# SilentStepStick-TMC2100_v13.net
KiCad netlist of a schematic drawn in EAGLE
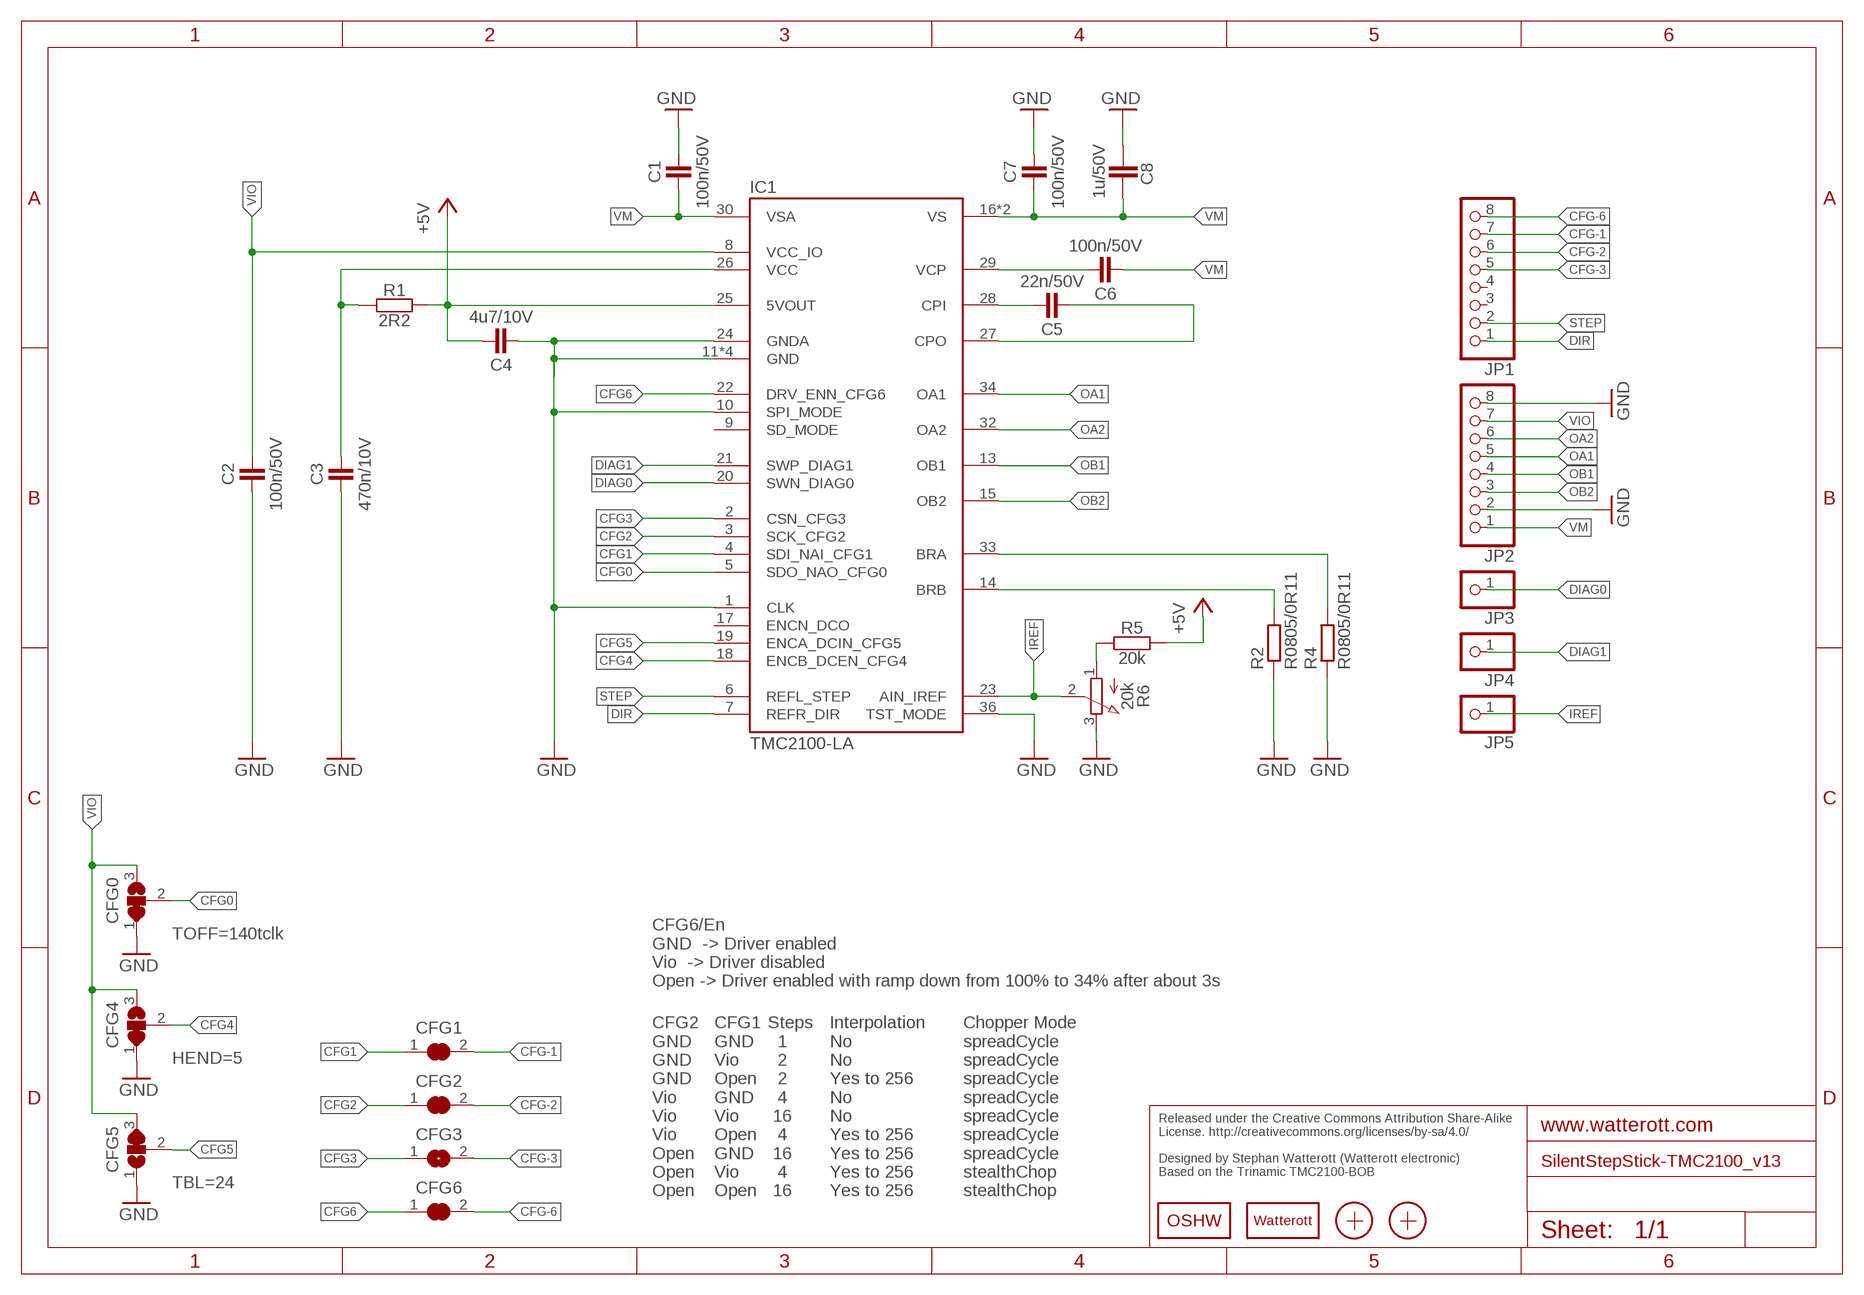
[diagram p0: schematic, sheet 1]

(export (version "E")
  (design (tool "Eeschema 10.0.6"))
  (components
    (comp (ref "C1")
      (value "100n/50V")
      (footprint "eagle-import:C0402")
      (libsource (lib "eagle-import") (part "CAPACITOR-0402"))
    )
    (comp (ref "C2")
      (value "100n/50V")
      (footprint "eagle-import:C0402")
      (libsource (lib "eagle-import") (part "CAPACITOR-0402"))
    )
    (comp (ref "C3")
      (value "470n/10V")
      (footprint "eagle-import:C0402")
      (libsource (lib "eagle-import") (part "CAPACITOR-0402"))
    )
    (comp (ref "C4")
      (value "4u7/10V")
      (footprint "eagle-import:C0402")
      (libsource (lib "eagle-import") (part "CAPACITOR-0402"))
    )
    (comp (ref "C5")
      (value "22n/50V")
      (footprint "eagle-import:C0402")
      (libsource (lib "eagle-import") (part "CAPACITOR-0402"))
    )
    (comp (ref "C6")
      (value "100n/50V")
      (footprint "eagle-import:C0402")
      (libsource (lib "eagle-import") (part "CAPACITOR-0402"))
    )
    (comp (ref "C7")
      (value "100n/50V")
      (footprint "eagle-import:C0402")
      (libsource (lib "eagle-import") (part "CAPACITOR-0402"))
    )
    (comp (ref "C8")
      (value "1u/50V")
      (footprint "eagle-import:C0603")
      (libsource (lib "eagle-import") (part "C-EUC0603"))
    )
    (comp (ref "CFG0")
      (value "JUMPER3-0201")
      (footprint "eagle-import:JUMPER3-0201")
      (libsource (lib "eagle-import") (part "JUMPER3-0201"))
    )
    (comp (ref "CFG1")
      (value "JUMPER2-0201")
      (footprint "eagle-import:JUMPER2-0201")
      (libsource (lib "eagle-import") (part "JUMPER2-0201"))
    )
    (comp (ref "CFG2")
      (value "JUMPER2-0201")
      (footprint "eagle-import:JUMPER2-0201")
      (libsource (lib "eagle-import") (part "JUMPER2-0201"))
    )
    (comp (ref "CFG3")
      (value "JUMPER2-0201")
      (footprint "eagle-import:JUMPER2-0201")
      (libsource (lib "eagle-import") (part "JUMPER2-0201"))
    )
    (comp (ref "CFG4")
      (value "JUMPER3-0201")
      (footprint "eagle-import:JUMPER3-0201")
      (libsource (lib "eagle-import") (part "JUMPER3-0201"))
    )
    (comp (ref "CFG5")
      (value "JUMPER3-0201")
      (footprint "eagle-import:JUMPER3-0201")
      (libsource (lib "eagle-import") (part "JUMPER3-0201"))
    )
    (comp (ref "CFG6")
      (value "JUMPER2-0201")
      (footprint "eagle-import:JUMPER2-0201")
      (libsource (lib "eagle-import") (part "JUMPER2-0201"))
    )
    (comp (ref "IC1")
      (value "TMC2100-LA")
      (footprint "eagle-import:QFN36-PAD")
      (libsource (lib "eagle-import") (part "TMC21X0-LA"))
    )
    (comp (ref "JP1")
      (value "PINHD-1X08_2.54-S")
      (footprint "eagle-import:1X08-S")
      (libsource (lib "eagle-import") (part "PINHD-1X08_2.54-S"))
    )
    (comp (ref "JP2")
      (value "PINHD-1X08_2.54-S")
      (footprint "eagle-import:1X08-S")
      (libsource (lib "eagle-import") (part "PINHD-1X08_2.54-S"))
    )
    (comp (ref "JP3")
      (value "PINHD-1X1")
      (footprint "eagle-import:1X01")
      (libsource (lib "eagle-import") (part "PINHD-1X1"))
    )
    (comp (ref "JP4")
      (value "PINHD-1X1")
      (footprint "eagle-import:1X01")
      (libsource (lib "eagle-import") (part "PINHD-1X1"))
    )
    (comp (ref "JP5")
      (value "PINHD-1X1")
      (footprint "eagle-import:1X01")
      (libsource (lib "eagle-import") (part "PINHD-1X1"))
    )
    (comp (ref "LOGO1")
      (value "OSHW_LOGOX0070")
      (footprint "eagle-import:OSHW_6X70")
      (libsource (lib "eagle-import") (part "OSHW_LOGOX0070"))
    )
    (comp (ref "LOGO2")
      (value "LOGO-S_PLACE_M")
      (footprint "eagle-import:SPARK_TPLACE_M")
      (libsource (lib "eagle-import") (part "LOGO-S_PLACE_M"))
    )
    (comp (ref "R1")
      (value "2R2")
      (footprint "eagle-import:C0402")
      (libsource (lib "eagle-import") (part "RESISTOR-0402"))
    )
    (comp (ref "R2")
      (value "R0805/0R11")
      (footprint "eagle-import:M0805")
      (libsource (lib "eagle-import") (part "R-EU_M0805"))
    )
    (comp (ref "R4")
      (value "R0805/0R11")
      (footprint "eagle-import:M0805")
      (libsource (lib "eagle-import") (part "R-EU_M0805"))
    )
    (comp (ref "R5")
      (value "20k")
      (footprint "eagle-import:C0402")
      (libsource (lib "eagle-import") (part "RESISTOR-0402"))
    )
    (comp (ref "R6")
      (value "20k")
      (footprint "eagle-import:POT_EVM3R")
      (libsource (lib "eagle-import") (part "POT-EVM3R"))
    )
    (comp (ref "X1")
      (value "PASSER-07")
      (footprint "eagle-import:PASSER_07MM")
      (libsource (lib "eagle-import") (part "PASSER-07"))
    )
    (comp (ref "X2")
      (value "PASSER-07")
      (footprint "eagle-import:PASSER_07MM")
      (libsource (lib "eagle-import") (part "PASSER-07"))
    )
  )
  (nets
    (net (code "1") (name "+5V") (class "Default")
      (node (ref "C4") (pin "2") (pinfunction "2_2") (pintype "passive"))
      (node (ref "IC1") (pin "25") (pinfunction "5VOUT_25") (pintype "power_in"))
      (node (ref "R1") (pin "2") (pinfunction "2_2") (pintype "passive"))
      (node (ref "R5") (pin "2") (pinfunction "2_2") (pintype "passive"))
    )
    (net (code "2") (name "CFG-1") (class "Default")
      (node (ref "CFG1") (pin "2") (pinfunction "2_2") (pintype "passive"))
      (node (ref "JP1") (pin "7") (pinfunction "7_7") (pintype "passive"))
    )
    (net (code "3") (name "CFG-2") (class "Default")
      (node (ref "CFG2") (pin "2") (pinfunction "2_2") (pintype "passive"))
      (node (ref "JP1") (pin "6") (pinfunction "6_6") (pintype "passive"))
    )
    (net (code "4") (name "CFG-3") (class "Default")
      (node (ref "CFG3") (pin "2") (pinfunction "2_2") (pintype "passive"))
      (node (ref "JP1") (pin "5") (pinfunction "5_5") (pintype "passive"))
    )
    (net (code "5") (name "CFG-6") (class "Default")
      (node (ref "CFG6") (pin "2") (pinfunction "2_2") (pintype "passive"))
      (node (ref "JP1") (pin "8") (pinfunction "8_8") (pintype "passive"))
    )
    (net (code "6") (name "CFG0") (class "Default")
      (node (ref "CFG0") (pin "2") (pinfunction "2_2") (pintype "passive"))
      (node (ref "IC1") (pin "5") (pinfunction "SDO_NAO_CFG0_5") (pintype "bidirectional"))
    )
    (net (code "7") (name "CFG1") (class "Default")
      (node (ref "CFG1") (pin "1") (pinfunction "1_1") (pintype "passive"))
      (node (ref "IC1") (pin "4") (pinfunction "SDI_NAI_CFG1_4") (pintype "bidirectional"))
    )
    (net (code "8") (name "CFG2") (class "Default")
      (node (ref "CFG2") (pin "1") (pinfunction "1_1") (pintype "passive"))
      (node (ref "IC1") (pin "3") (pinfunction "SCK_CFG2_3") (pintype "bidirectional"))
    )
    (net (code "9") (name "CFG3") (class "Default")
      (node (ref "CFG3") (pin "1") (pinfunction "1_1") (pintype "passive"))
      (node (ref "IC1") (pin "2") (pinfunction "CSN_CFG3_2") (pintype "bidirectional"))
    )
    (net (code "10") (name "CFG4") (class "Default")
      (node (ref "CFG4") (pin "2") (pinfunction "2_2") (pintype "passive"))
      (node (ref "IC1") (pin "18") (pinfunction "ENCB_DCEN_CFG4_18") (pintype "bidirectional"))
    )
    (net (code "11") (name "CFG5") (class "Default")
      (node (ref "CFG5") (pin "2") (pinfunction "2_2") (pintype "passive"))
      (node (ref "IC1") (pin "19") (pinfunction "ENCA_DCIN_CFG5_19") (pintype "bidirectional"))
    )
    (net (code "12") (name "CFG6") (class "Default")
      (node (ref "CFG6") (pin "1") (pinfunction "1_1") (pintype "passive"))
      (node (ref "IC1") (pin "22") (pinfunction "DRV_ENN_CFG6_22") (pintype "bidirectional"))
    )
    (net (code "13") (name "DIAG0") (class "Default")
      (node (ref "IC1") (pin "20") (pinfunction "SWN_DIAG0_20") (pintype "bidirectional"))
      (node (ref "JP3") (pin "1") (pinfunction "1_1") (pintype "passive"))
    )
    (net (code "14") (name "DIAG1") (class "Default")
      (node (ref "IC1") (pin "21") (pinfunction "SWP_DIAG1_21") (pintype "bidirectional"))
      (node (ref "JP4") (pin "1") (pinfunction "1_1") (pintype "passive"))
    )
    (net (code "15") (name "DIR") (class "Default")
      (node (ref "IC1") (pin "7") (pinfunction "REFR_DIR_7") (pintype "bidirectional"))
      (node (ref "JP1") (pin "1") (pinfunction "1_1") (pintype "passive"))
    )
    (net (code "16") (name "GND") (class "Default")
      (node (ref "C1") (pin "2") (pinfunction "2_2") (pintype "passive"))
      (node (ref "C2") (pin "1") (pinfunction "1_1") (pintype "passive"))
      (node (ref "C3") (pin "1") (pinfunction "1_1") (pintype "passive"))
      (node (ref "C4") (pin "1") (pinfunction "1_1") (pintype "passive"))
      (node (ref "C7") (pin "2") (pinfunction "2_2") (pintype "passive"))
      (node (ref "C8") (pin "2") (pinfunction "2_2") (pintype "passive"))
      (node (ref "CFG0") (pin "1") (pinfunction "1_1") (pintype "passive"))
      (node (ref "CFG4") (pin "1") (pinfunction "1_1") (pintype "passive"))
      (node (ref "CFG5") (pin "1") (pinfunction "1_1") (pintype "passive"))
      (node (ref "IC1") (pin "1") (pinfunction "CLK_1") (pintype "bidirectional"))
      (node (ref "IC1") (pin "10") (pinfunction "SPI_MODE_10") (pintype "bidirectional"))
      (node (ref "IC1") (pin "11") (pinfunction "GND_11") (pintype "power_in"))
      (node (ref "IC1") (pin "12") (pinfunction "GND_12") (pintype "power_in"))
      (node (ref "IC1") (pin "24") (pinfunction "GNDA_24") (pintype "power_in"))
      (node (ref "IC1") (pin "35") (pinfunction "GND_35") (pintype "power_in"))
      (node (ref "IC1") (pin "36") (pinfunction "TST_MODE_36") (pintype "bidirectional"))
      (node (ref "IC1") (pin "TP") (pinfunction "GND_TP") (pintype "power_in"))
      (node (ref "JP2") (pin "2") (pinfunction "2_2") (pintype "passive"))
      (node (ref "JP2") (pin "8") (pinfunction "8_8") (pintype "passive"))
      (node (ref "R2") (pin "1") (pinfunction "1_1") (pintype "passive"))
      (node (ref "R4") (pin "1") (pinfunction "1_1") (pintype "passive"))
      (node (ref "R6") (pin "3") (pinfunction "E_3") (pintype "passive"))
    )
    (net (code "17") (name "IREF") (class "Default")
      (node (ref "IC1") (pin "23") (pinfunction "AIN_IREF_23") (pintype "passive"))
      (node (ref "JP5") (pin "1") (pinfunction "1_1") (pintype "passive"))
      (node (ref "R6") (pin "2") (pinfunction "S_2") (pintype "passive"))
    )
    (net (code "18") (name "Net-(IC1-BRA)") (class "Default")
      (node (ref "IC1") (pin "33") (pinfunction "BRA_33") (pintype "output"))
      (node (ref "R4") (pin "2") (pinfunction "2_2") (pintype "passive"))
    )
    (net (code "19") (name "Net-(IC1-BRB)") (class "Default")
      (node (ref "IC1") (pin "14") (pinfunction "BRB_14") (pintype "output"))
      (node (ref "R2") (pin "2") (pinfunction "2_2") (pintype "passive"))
    )
    (net (code "20") (name "Net-(IC1-CPI)") (class "Default")
      (node (ref "C5") (pin "2") (pinfunction "2_2") (pintype "passive"))
      (node (ref "IC1") (pin "28") (pinfunction "CPI_28") (pintype "passive"))
    )
    (net (code "21") (name "Net-(IC1-CPO)") (class "Default")
      (node (ref "C5") (pin "1") (pinfunction "1_1") (pintype "passive"))
      (node (ref "IC1") (pin "27") (pinfunction "CPO_27") (pintype "passive"))
    )
    (net (code "22") (name "Net-(IC1-VCC)") (class "Default")
      (node (ref "C3") (pin "2") (pinfunction "2_2") (pintype "passive"))
      (node (ref "IC1") (pin "26") (pinfunction "VCC_26") (pintype "power_in"))
      (node (ref "R1") (pin "1") (pinfunction "1_1") (pintype "passive"))
    )
    (net (code "23") (name "Net-(IC1-VCP)") (class "Default")
      (node (ref "C6") (pin "2") (pinfunction "2_2") (pintype "passive"))
      (node (ref "IC1") (pin "29") (pinfunction "VCP_29") (pintype "passive"))
    )
    (net (code "24") (name "Net-(R6-A)") (class "Default")
      (node (ref "R5") (pin "1") (pinfunction "1_1") (pintype "passive"))
      (node (ref "R6") (pin "1") (pinfunction "A_1") (pintype "passive"))
    )
    (net (code "25") (name "OA1") (class "Default")
      (node (ref "IC1") (pin "34") (pinfunction "OA1_34") (pintype "output"))
      (node (ref "JP2") (pin "5") (pinfunction "5_5") (pintype "passive"))
    )
    (net (code "26") (name "OA2") (class "Default")
      (node (ref "IC1") (pin "32") (pinfunction "OA2_32") (pintype "output"))
      (node (ref "JP2") (pin "6") (pinfunction "6_6") (pintype "passive"))
    )
    (net (code "27") (name "OB1") (class "Default")
      (node (ref "IC1") (pin "13") (pinfunction "OB1_13") (pintype "output"))
      (node (ref "JP2") (pin "4") (pinfunction "4_4") (pintype "passive"))
    )
    (net (code "28") (name "OB2") (class "Default")
      (node (ref "IC1") (pin "15") (pinfunction "OB2_15") (pintype "output"))
      (node (ref "JP2") (pin "3") (pinfunction "3_3") (pintype "passive"))
    )
    (net (code "29") (name "STEP") (class "Default")
      (node (ref "IC1") (pin "6") (pinfunction "REFL_STEP_6") (pintype "bidirectional"))
      (node (ref "JP1") (pin "2") (pinfunction "2_2") (pintype "passive"))
    )
    (net (code "30") (name "VIO") (class "Default")
      (node (ref "C2") (pin "2") (pinfunction "2_2") (pintype "passive"))
      (node (ref "CFG0") (pin "3") (pinfunction "3_3") (pintype "passive"))
      (node (ref "CFG4") (pin "3") (pinfunction "3_3") (pintype "passive"))
      (node (ref "CFG5") (pin "3") (pinfunction "3_3") (pintype "passive"))
      (node (ref "IC1") (pin "8") (pinfunction "VCC_IO_8") (pintype "power_in"))
      (node (ref "JP2") (pin "7") (pinfunction "7_7") (pintype "passive"))
    )
    (net (code "31") (name "VM") (class "Default")
      (node (ref "C1") (pin "1") (pinfunction "1_1") (pintype "passive"))
      (node (ref "C6") (pin "1") (pinfunction "1_1") (pintype "passive"))
      (node (ref "C7") (pin "1") (pinfunction "1_1") (pintype "passive"))
      (node (ref "C8") (pin "1") (pinfunction "1_1") (pintype "passive"))
      (node (ref "IC1") (pin "16") (pinfunction "VS_16") (pintype "power_in"))
      (node (ref "IC1") (pin "30") (pinfunction "VSA_30") (pintype "power_in"))
      (node (ref "IC1") (pin "31") (pinfunction "VS_31") (pintype "power_in"))
      (node (ref "JP2") (pin "1") (pinfunction "1_1") (pintype "passive"))
    )
    (net (code "32") (name "unconnected-(IC1-ENCN_DCO-Pad17)") (class "Default")
      (node (ref "IC1") (pin "17") (pinfunction "ENCN_DCO_17") (pintype "bidirectional"))
    )
    (net (code "33") (name "unconnected-(IC1-SD_MODE-Pad9)") (class "Default")
      (node (ref "IC1") (pin "9") (pinfunction "SD_MODE_9") (pintype "bidirectional"))
    )
    (net (code "34") (name "unconnected-(JP1-Pad3)") (class "Default")
      (node (ref "JP1") (pin "3") (pinfunction "3_3") (pintype "passive"))
    )
    (net (code "35") (name "unconnected-(JP1-Pad4)") (class "Default")
      (node (ref "JP1") (pin "4") (pinfunction "4_4") (pintype "passive"))
    )
  )
)
